# MP28167GQ-Z_Buck-Boost_Switching_Regulat.net
KiCad netlist of a schematic drawn in Altium Designer
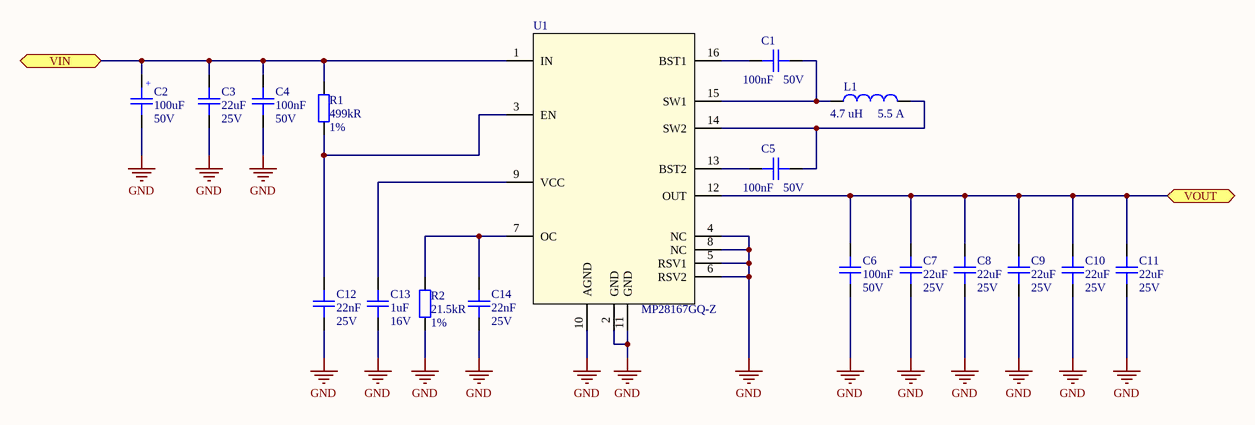
[diagram p0: MP28167GQ-Z_Buck-Boost Switching Regulator.SchDoc]

(export (version "E")
  (design (tool "Eeschema 10.0.6"))
  (components
    (comp (ref "C1")
      (value "CAP CER 0.1UF 50V X7R 0402")
      (footprint "C0402")
      (description "0.1µF ±10% 50V Ceramic Capacitor X7R 0402 (1005 Metric)")
      (fields
        (field (name "MANUFACTURER") "TDK")
        (field (name "MANUFACTURER PART NUMBER") "CGA2B3X7R1H104K050BB")
        (field (name "CAPACITANCE") "100nF")
        (field (name "VOLTAGE") "50V")
      )
      (libsource (lib "Control_Board_Model") (part "CAP CER 0.1UF 50V X7R 0402"))
    )
    (comp (ref "C2")
      (value "CAP ALUM 100UF 20% 50V SMD")
      (footprint "WCAP-ASLI_8.3X10.5")
      (description "100 µF 50 V Aluminum Electrolytic Capacitors Radial, Can - SMD - 2000 Hrs @ 105°C")
      (fields
        (field (name "MANUFACTURER") "Wurth Elektronik")
        (field (name "MANUFACTURER PART NUMBER") "865080653016")
        (field (name "CAPACITANCE") "100uF")
        (field (name "RATED VOLTAGE") "50V")
      )
      (libsource (lib "Control_Board_Model") (part "CAP ALUM 100UF 20% 50V SMD"))
    )
    (comp (ref "C3")
      (value "CAP CER 22UF 25V X5R 0805")
      (footprint "C0805")
      (description "22µF ±20% 25V Ceramic Capacitor X5R 0805 (2012 Metric)")
      (fields
        (field (name "MANUFACTURER") "Yageo")
        (field (name "MANUFACTURER PART NUMBER") "CC0805MKX5R8BB226")
        (field (name "CAPACITANCE") "22uF")
        (field (name "VOLTAGE RATING") "25V")
      )
      (libsource (lib "Control_Board_Model") (part "CAP CER 22UF 25V X5R 0805"))
    )
    (comp (ref "C4")
      (value "CAP CER 0.1UF 50V X7R 0402")
      (footprint "C0402")
      (description "0.1µF ±10% 50V Ceramic Capacitor X7R 0402 (1005 Metric)")
      (fields
        (field (name "MANUFACTURER") "TDK")
        (field (name "MANUFACTURER PART NUMBER") "CGA2B3X7R1H104K050BB")
        (field (name "CAPACITANCE") "100nF")
        (field (name "VOLTAGE") "50V")
      )
      (libsource (lib "Control_Board_Model") (part "CAP CER 0.1UF 50V X7R 0402"))
    )
    (comp (ref "C5")
      (value "CAP CER 0.1UF 50V X7R 0402")
      (footprint "C0402")
      (description "0.1µF ±10% 50V Ceramic Capacitor X7R 0402 (1005 Metric)")
      (fields
        (field (name "MANUFACTURER") "TDK")
        (field (name "MANUFACTURER PART NUMBER") "CGA2B3X7R1H104K050BB")
        (field (name "CAPACITANCE") "100nF")
        (field (name "VOLTAGE") "50V")
      )
      (libsource (lib "Control_Board_Model") (part "CAP CER 0.1UF 50V X7R 0402"))
    )
    (comp (ref "C6")
      (value "CAP CER 0.1UF 50V X7R 0402")
      (footprint "C0402")
      (description "0.1µF ±10% 50V Ceramic Capacitor X7R 0402 (1005 Metric)")
      (fields
        (field (name "MANUFACTURER") "TDK")
        (field (name "MANUFACTURER PART NUMBER") "CGA2B3X7R1H104K050BB")
        (field (name "CAPACITANCE") "100nF")
        (field (name "VOLTAGE") "50V")
      )
      (libsource (lib "Control_Board_Model") (part "CAP CER 0.1UF 50V X7R 0402"))
    )
    (comp (ref "C7")
      (value "CAP CER 22UF 25V X5R 0805")
      (footprint "C0805")
      (description "22µF ±20% 25V Ceramic Capacitor X5R 0805 (2012 Metric)")
      (fields
        (field (name "MANUFACTURER") "Yageo")
        (field (name "MANUFACTURER PART NUMBER") "CC0805MKX5R8BB226")
        (field (name "CAPACITANCE") "22uF")
        (field (name "VOLTAGE RATING") "25V")
      )
      (libsource (lib "Control_Board_Model") (part "CAP CER 22UF 25V X5R 0805"))
    )
    (comp (ref "C8")
      (value "CAP CER 22UF 25V X5R 0805")
      (footprint "C0805")
      (description "22µF ±20% 25V Ceramic Capacitor X5R 0805 (2012 Metric)")
      (fields
        (field (name "MANUFACTURER") "Yageo")
        (field (name "MANUFACTURER PART NUMBER") "CC0805MKX5R8BB226")
        (field (name "CAPACITANCE") "22uF")
        (field (name "VOLTAGE RATING") "25V")
      )
      (libsource (lib "Control_Board_Model") (part "CAP CER 22UF 25V X5R 0805"))
    )
    (comp (ref "C9")
      (value "CAP CER 22UF 25V X5R 0805")
      (footprint "C0805")
      (description "22µF ±20% 25V Ceramic Capacitor X5R 0805 (2012 Metric)")
      (fields
        (field (name "MANUFACTURER") "Yageo")
        (field (name "MANUFACTURER PART NUMBER") "CC0805MKX5R8BB226")
        (field (name "CAPACITANCE") "22uF")
        (field (name "VOLTAGE RATING") "25V")
      )
      (libsource (lib "Control_Board_Model") (part "CAP CER 22UF 25V X5R 0805"))
    )
    (comp (ref "C10")
      (value "CAP CER 22UF 25V X5R 0805")
      (footprint "C0805")
      (description "22µF ±20% 25V Ceramic Capacitor X5R 0805 (2012 Metric)")
      (fields
        (field (name "MANUFACTURER") "Yageo")
        (field (name "MANUFACTURER PART NUMBER") "CC0805MKX5R8BB226")
        (field (name "CAPACITANCE") "22uF")
        (field (name "VOLTAGE RATING") "25V")
      )
      (libsource (lib "Control_Board_Model") (part "CAP CER 22UF 25V X5R 0805"))
    )
    (comp (ref "C11")
      (value "CAP CER 22UF 25V X5R 0805")
      (footprint "C0805")
      (description "22µF ±20% 25V Ceramic Capacitor X5R 0805 (2012 Metric)")
      (fields
        (field (name "MANUFACTURER") "Yageo")
        (field (name "MANUFACTURER PART NUMBER") "CC0805MKX5R8BB226")
        (field (name "CAPACITANCE") "22uF")
        (field (name "VOLTAGE RATING") "25V")
      )
      (libsource (lib "Control_Board_Model") (part "CAP CER 22UF 25V X5R 0805"))
    )
    (comp (ref "C12")
      (value "CAP CER 0.022UF 25V X7R 0402")
      (footprint "C0402")
      (description "0.022µF ±10% 25V Ceramic Capacitor X7R 0402 (1005 Metric)")
      (fields
        (field (name "MANUFACTURER") "TDK")
        (field (name "MANUFACTURER PART NUMBER") "CGA2B2X7R1E223K050BA")
        (field (name "CAPACITANCE") "22nF")
        (field (name "VOLTAGE RATING") "25V")
      )
      (libsource (lib "Control_Board_Model") (part "CAP CER 0.022UF 25V X7R 0402"))
    )
    (comp (ref "C13")
      (value "CAP CER 1UF 16V X5R 0402")
      (footprint "C0402")
      (description "1µF ±10% 16V Ceramic Capacitor X5R 0402 (1005 Metric)")
      (fields
        (field (name "MANUFACTURER") "Yageo")
        (field (name "MANUFACTURER PART NUMBER") "CC0402KRX5R7BB105")
        (field (name "CAPACITANCE") "1uF")
        (field (name "VOLTAGE RATING") "16V")
      )
      (libsource (lib "Control_Board_Model") (part "CAP CER 1UF 16V X5R 0402"))
    )
    (comp (ref "C14")
      (value "CAP CER 0.022UF 25V X7R 0402")
      (footprint "C0402")
      (description "0.022µF ±10% 25V Ceramic Capacitor X7R 0402 (1005 Metric)")
      (fields
        (field (name "MANUFACTURER") "TDK")
        (field (name "MANUFACTURER PART NUMBER") "CGA2B2X7R1E223K050BA")
        (field (name "CAPACITANCE") "22nF")
        (field (name "VOLTAGE RATING") "25V")
      )
      (libsource (lib "Control_Board_Model") (part "CAP CER 0.022UF 25V X7R 0402"))
    )
    (comp (ref "L1")
      (value "FIXED IND 4.7UH 5.5A 34.5MOHM SM")
      (footprint "IND_WE_MAPI")
      (fields
        (field (name "MANUFACTURER") "Wurth Elektronik")
        (field (name "MANUFACTURER PART NUMBER") "74438367047")
        (field (name "TOLERANCE") "20 %")
        (field (name "INDUCTANCE") "4.7 uH")
        (field (name "MAXIMUM DC CURRENT") "5.5 A")
      )
      (libsource (lib "Control_Board_Model") (part "FIXED IND 4.7UH 5.5A 34.5MOHM SM"))
    )
    (comp (ref "R1")
      (value "RES SMD 499K OHM 1% 1/16W 0402")
      (footprint "R0402")
      (description "499 kOhms ±1% 0.063W, 1/16W Chip Resistor 0402 (1005 Metric) Moisture Resistant Thick Film")
      (fields
        (field (name "MANUFACTURER") "Yageo")
        (field (name "MANUFACTURER PART NUMBER") "RC0402FR-07499KL")
        (field (name "RESISTANCE") "499kR")
        (field (name "TOLERANCE") "1%")
      )
      (libsource (lib "Control_Board_Model") (part "RES SMD 499K OHM 1% 1/16W 0402"))
    )
    (comp (ref "R2")
      (value "RES SMD 21.5K OHM 1% 1/16W 0402")
      (footprint "R0402")
      (description "21.5 kOhms ±1% 0.063W, 1/16W Chip Resistor 0402 (1005 Metric) Moisture Resistant Thick Film")
      (fields
        (field (name "MANUFACTURER") "Yageo")
        (field (name "MANUFACTURER PART NUMBER") "RC0402FR-0721K5L")
        (field (name "RESISTANCE") "21.5kR")
        (field (name "TOLERANCE") "1%")
      )
      (libsource (lib "Control_Board_Model") (part "RES SMD 21.5K OHM 1% 1/16W 0402"))
    )
    (comp (ref "U1")
      (value "MP28167GQ-Z")
      (footprint "QFN16_3X3")
      (description "Buck-Boost Switching Regulator IC Positive Fixed 5V 1 Output 3A 16-PowerVFQFN")
      (fields (field (name "MANUFACTURER") "Monolithic Power Systems Inc."))
      (libsource (lib "Control_Board_Model") (part "IC MP28167GQ-Z 2.8V-22V VIN, 3A IOUT, 4-SWITCH"))
    )
  )
  (nets
    (net (code "1") (name "/VIN") (class "Default")
      (node (ref "C2") (pin "1") (pinfunction "1_1") (pintype "passive"))
      (node (ref "C3") (pin "2") (pinfunction "2_2") (pintype "passive"))
      (node (ref "C4") (pin "2") (pinfunction "2_2") (pintype "passive"))
      (node (ref "R1") (pin "2") (pinfunction "2_2") (pintype "passive"))
      (node (ref "U1") (pin "1") (pinfunction "IN_1") (pintype "power_in"))
    )
    (net (code "2") (name "/VOUT") (class "Default")
      (node (ref "C10") (pin "2") (pinfunction "2_2") (pintype "passive"))
      (node (ref "C11") (pin "2") (pinfunction "2_2") (pintype "passive"))
      (node (ref "C6") (pin "2") (pinfunction "2_2") (pintype "passive"))
      (node (ref "C7") (pin "2") (pinfunction "2_2") (pintype "passive"))
      (node (ref "C8") (pin "2") (pinfunction "2_2") (pintype "passive"))
      (node (ref "C9") (pin "2") (pinfunction "2_2") (pintype "passive"))
      (node (ref "U1") (pin "12") (pinfunction "OUT_12") (pintype "power_in"))
    )
    (net (code "3") (name "GND") (class "Default")
      (node (ref "C10") (pin "1") (pinfunction "1_1") (pintype "passive"))
      (node (ref "C11") (pin "1") (pinfunction "1_1") (pintype "passive"))
      (node (ref "C12") (pin "1") (pinfunction "1_1") (pintype "passive"))
      (node (ref "C13") (pin "1") (pinfunction "1_1") (pintype "passive"))
      (node (ref "C14") (pin "1") (pinfunction "1_1") (pintype "passive"))
      (node (ref "C2") (pin "2") (pinfunction "2_2") (pintype "passive"))
      (node (ref "C3") (pin "1") (pinfunction "1_1") (pintype "passive"))
      (node (ref "C4") (pin "1") (pinfunction "1_1") (pintype "passive"))
      (node (ref "C6") (pin "1") (pinfunction "1_1") (pintype "passive"))
      (node (ref "C7") (pin "1") (pinfunction "1_1") (pintype "passive"))
      (node (ref "C8") (pin "1") (pinfunction "1_1") (pintype "passive"))
      (node (ref "C9") (pin "1") (pinfunction "1_1") (pintype "passive"))
      (node (ref "R2") (pin "2") (pinfunction "2_2") (pintype "passive"))
      (node (ref "U1") (pin "10") (pinfunction "AGND_10") (pintype "power_in"))
      (node (ref "U1") (pin "11") (pinfunction "GND_11") (pintype "power_in"))
      (node (ref "U1") (pin "2") (pinfunction "GND_2") (pintype "power_in"))
      (node (ref "U1") (pin "4") (pinfunction "NC_4") (pintype "power_in"))
      (node (ref "U1") (pin "5") (pinfunction "RSV1_5") (pintype "power_in"))
      (node (ref "U1") (pin "6") (pinfunction "RSV2_6") (pintype "power_in"))
      (node (ref "U1") (pin "8") (pinfunction "NC_8") (pintype "power_in"))
    )
    (net (code "4") (name "Net-(U1-BST1)") (class "Default")
      (node (ref "C1") (pin "1") (pinfunction "1_1") (pintype "passive"))
      (node (ref "U1") (pin "16") (pinfunction "BST1_16") (pintype "power_in"))
    )
    (net (code "5") (name "Net-(U1-BST2)") (class "Default")
      (node (ref "C5") (pin "1") (pinfunction "1_1") (pintype "passive"))
      (node (ref "U1") (pin "13") (pinfunction "BST2_13") (pintype "power_in"))
    )
    (net (code "6") (name "Net-(U1-EN)") (class "Default")
      (node (ref "C12") (pin "2") (pinfunction "2_2") (pintype "passive"))
      (node (ref "R1") (pin "1") (pinfunction "1_1") (pintype "passive"))
      (node (ref "U1") (pin "3") (pinfunction "EN_3") (pintype "power_in"))
    )
    (net (code "7") (name "Net-(U1-OC)") (class "Default")
      (node (ref "C14") (pin "2") (pinfunction "2_2") (pintype "passive"))
      (node (ref "R2") (pin "1") (pinfunction "1_1") (pintype "passive"))
      (node (ref "U1") (pin "7") (pinfunction "OC_7") (pintype "power_in"))
    )
    (net (code "8") (name "Net-(U1-SW1)") (class "Default")
      (node (ref "C1") (pin "2") (pinfunction "2_2") (pintype "passive"))
      (node (ref "L1") (pin "1") (pinfunction "1_1") (pintype "passive"))
      (node (ref "U1") (pin "15") (pinfunction "SW1_15") (pintype "power_in"))
    )
    (net (code "9") (name "Net-(U1-SW2)") (class "Default")
      (node (ref "C5") (pin "2") (pinfunction "2_2") (pintype "passive"))
      (node (ref "L1") (pin "2") (pinfunction "2_2") (pintype "passive"))
      (node (ref "U1") (pin "14") (pinfunction "SW2_14") (pintype "power_in"))
    )
    (net (code "10") (name "Net-(U1-VCC)") (class "Default")
      (node (ref "C13") (pin "2") (pinfunction "2_2") (pintype "passive"))
      (node (ref "U1") (pin "9") (pinfunction "VCC_9") (pintype "power_in"))
    )
  )
)
